# ProPrj_minibal.net
KiCad netlist of a schematic drawn in EasyEDA Pro
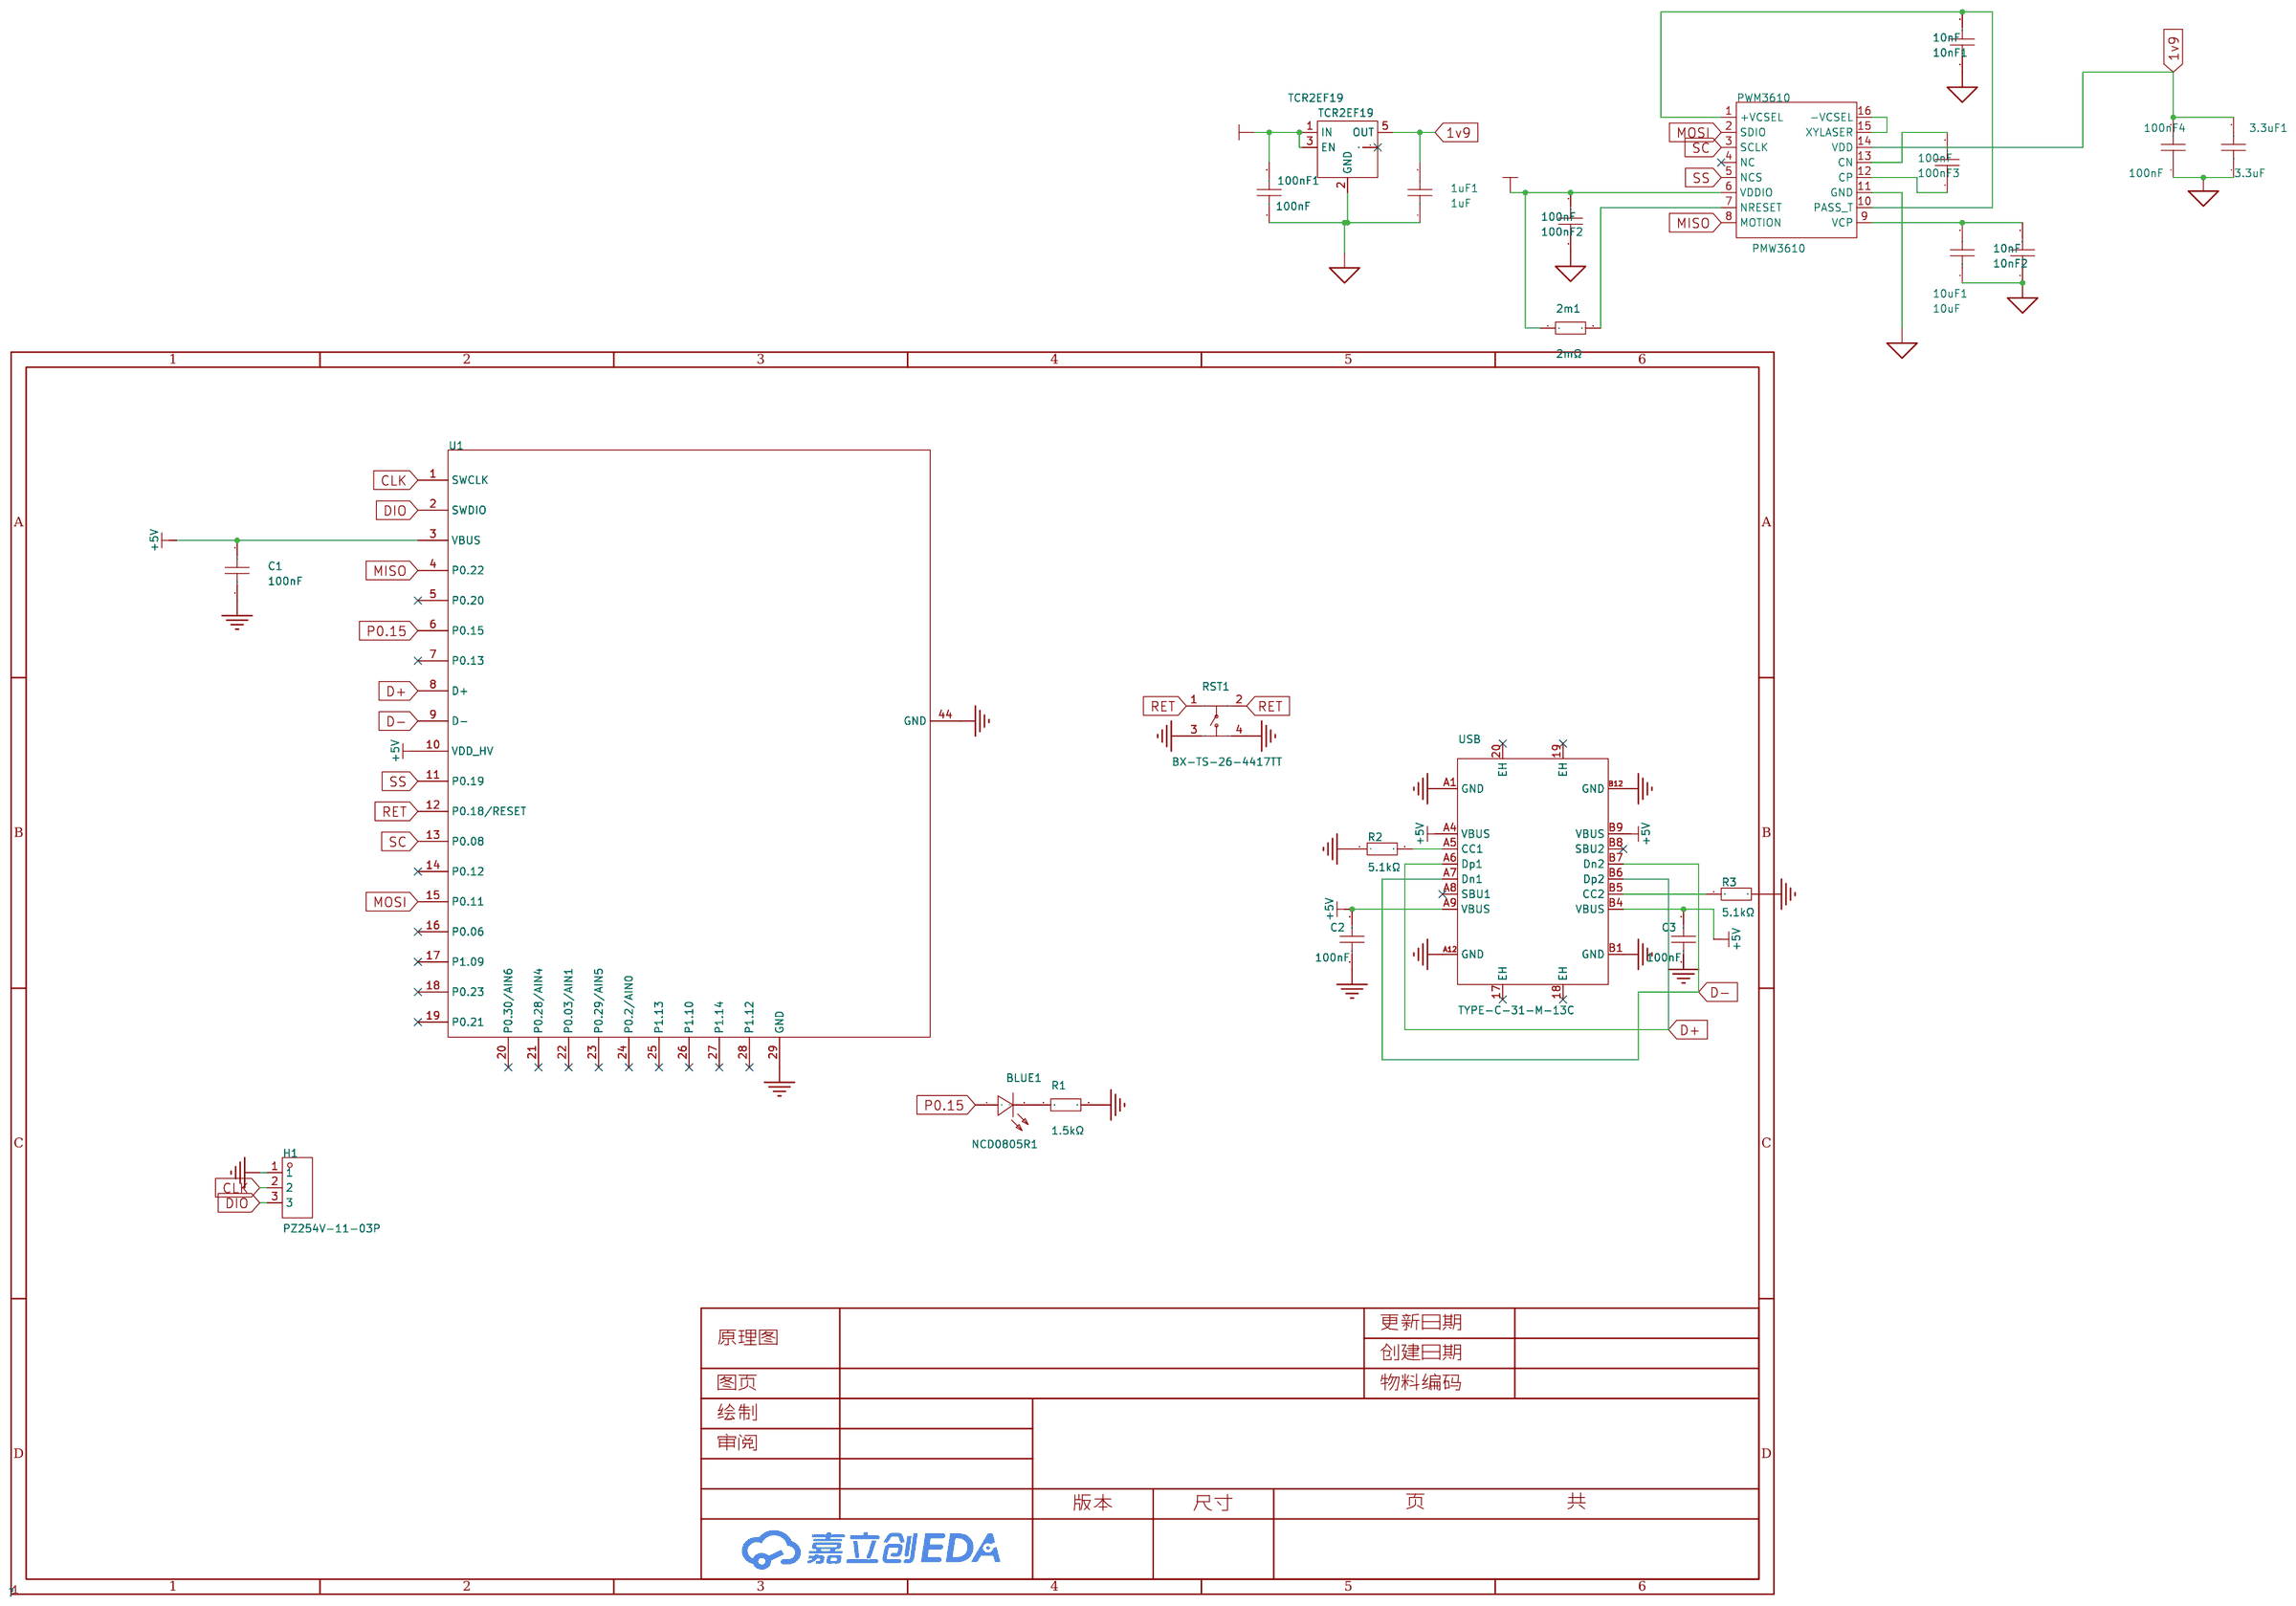
[diagram p0: schematic sheet]

(export (version "E")
  (design (tool "Eeschema 10.0.6"))
  (components
    (comp (ref "1uF1")
      (value "1uF")
      (footprint "easyedapro:C0603")
      (fields
        (field (name "Manufacturer Part") "CL21B105KBFNNNE")
        (field (name "Manufacturer") "SAMSUNG(三星)")
      )
      (libsource (lib "easyedapro") (part "CapAcitance"))
    )
    (comp (ref "2m1")
      (value "2mΩ")
      (fields (field (name "Manufacturer Part") "RLM10FTSMR002") (field (name "Manufacturer") "大毅科技"))
      (libsource (lib "easyedapro") (part "电阻"))
    )
    (comp (ref "3.3uF1")
      (value "3.3uF")
      (footprint "easyedapro:C0603")
      (fields (field (name "Manufacturer Part") "0805B335K160NT") (field (name "Manufacturer") "FH(风华)"))
      (libsource (lib "easyedapro") (part "CapAcitance"))
    )
    (comp (ref "10nF1")
      (value "10nF")
      (footprint "easyedapro:C0603")
      (fields
        (field (name "Manufacturer Part") "CC0805KRX7R9BB103")
        (field (name "Manufacturer") "YAGEO(国巨)")
      )
      (libsource (lib "easyedapro") (part "CapAcitance"))
    )
    (comp (ref "10nF2")
      (value "10nF")
      (footprint "easyedapro:C0603")
      (fields
        (field (name "Manufacturer Part") "CC0805KRX7R9BB103")
        (field (name "Manufacturer") "YAGEO(国巨)")
      )
      (libsource (lib "easyedapro") (part "CapAcitance"))
    )
    (comp (ref "10uF1")
      (value "10uF")
      (footprint "easyedapro:C0603")
      (fields
        (field (name "Manufacturer Part") "CL21A106KOQNNNE")
        (field (name "Manufacturer") "SAMSUNG(三星)")
      )
      (libsource (lib "easyedapro") (part "CapAcitance"))
    )
    (comp (ref "100nF1")
      (value "100nF")
      (footprint "easyedapro:C0603")
      (fields (field (name "Manufacturer Part") "0805B104K500NT") (field (name "Manufacturer") "FH(风华)"))
      (libsource (lib "easyedapro") (part "CapAcitance"))
    )
    (comp (ref "100nF2")
      (value "100nF")
      (footprint "easyedapro:C0603")
      (fields (field (name "Manufacturer Part") "0805B104K500NT") (field (name "Manufacturer") "FH(风华)"))
      (libsource (lib "easyedapro") (part "CapAcitance"))
    )
    (comp (ref "100nF3")
      (value "100nF")
      (footprint "easyedapro:C0603")
      (fields (field (name "Manufacturer Part") "0805B104K500NT") (field (name "Manufacturer") "FH(风华)"))
      (libsource (lib "easyedapro") (part "CapAcitance"))
    )
    (comp (ref "100nF4")
      (value "100nF")
      (footprint "easyedapro:C0603")
      (fields (field (name "Manufacturer Part") "0805B104K500NT") (field (name "Manufacturer") "FH(风华)"))
      (libsource (lib "easyedapro") (part "CapAcitance"))
    )
    (comp (ref "BLUE1")
      (value "NCD0805R1")
      (footprint "easyedapro:LED0805-R-RD")
      (fields (field (name "Manufacturer") "国星光电"))
      (libsource (lib "easyedapro") (part "FC-2012HRK-620D"))
    )
    (comp (ref "C1")
      (value "100nF")
      (footprint "easyedapro:C0603")
      (fields
        (field (name "Manufacturer Part") "CC0603KRX7R9BB104")
        (field (name "Manufacturer") "YAGEO(国巨)")
      )
      (libsource (lib "easyedapro") (part "CapAcitance"))
    )
    (comp (ref "C2")
      (value "100nF")
      (footprint "easyedapro:C0603")
      (libsource (lib "easyedapro") (part "CapAcitance"))
    )
    (comp (ref "C3")
      (value "100nF")
      (footprint "easyedapro:C0603")
      (libsource (lib "easyedapro") (part "CapAcitance"))
    )
    (comp (ref "H1")
      (value "PZ254V-11-03P")
      (footprint "easyedapro:HDR-TH_3P-P2.54-V-M")
      (fields (field (name "Manufacturer") "XFCN(兴飞)"))
      (libsource (lib "easyedapro") (part "PZ254V-11-03P_C2937625"))
    )
    (comp (ref "PWM3610")
      (value "PMW3610")
      (footprint "easyedapro:mylib:PMW3610")
      (libsource (lib "easyedapro") (part "mysymbol_PMW3610"))
    )
    (comp (ref "R1")
      (value "1.5kΩ")
      (footprint "easyedapro:R0805")
      (description "电阻类型:厚膜电阻;阻值:1.5kΩ;精度:±1%;功率:125mW;最大工作电压:150V;温度系数:±100ppm/°C;")
      (fields
        (field (name "Manufacturer Part") "0805W8F1501T5E")
        (field (name "Manufacturer") "UNI-ROYAL(厚声)")
      )
      (libsource (lib "easyedapro") (part "0805W8F1501T5E"))
    )
    (comp (ref "R2")
      (value "5.1kΩ")
      (footprint "easyedapro:R0805")
      (description "电阻类型:厚膜电阻;阻值:5.1kΩ;精度:±1%;功率:125mW;最大工作电压:150V;温度系数:±100ppm/°C;")
      (fields
        (field (name "Manufacturer Part") "0805W8F5101T5E")
        (field (name "Manufacturer") "UNI-ROYAL(厚声)")
      )
      (libsource (lib "easyedapro") (part "0805W8F5101T5E"))
    )
    (comp (ref "R3")
      (value "5.1kΩ")
      (footprint "easyedapro:R0805")
      (description "电阻类型:厚膜电阻;阻值:5.1kΩ;精度:±1%;功率:125mW;最大工作电压:150V;温度系数:±100ppm/°C;")
      (fields
        (field (name "Manufacturer Part") "0805W8F5101T5E")
        (field (name "Manufacturer") "UNI-ROYAL(厚声)")
      )
      (libsource (lib "easyedapro") (part "0805W8F5101T5E"))
    )
    (comp (ref "RST1")
      (value "BX-TS-26-4417TT")
      (footprint "easyedapro:SW-SMD_4P-L5.2-W5.2-P3.70-LS6.5")
      (fields (field (name "Manufacturer") "Bossie(博锡)"))
      (libsource (lib "easyedapro") (part "BX-TS-26-4417TT"))
    )
    (comp (ref "TCR2EF19")
      (value "TCR2EF19")
      (footprint "easyedapro:Package_TO_SOT_SMD:SOT-23-5")
      (libsource (lib "easyedapro") (part "Regulator_Linear_TLV70218_SOT23-5"))
    )
    (comp (ref "U1")
      (value "N52840")
      (footprint "easyedapro:52840MICRO-v1")
      (libsource (lib "easyedapro") (part "52840micro"))
    )
    (comp (ref "USB")
      (value "TYPE-C-31-M-13C")
      (footprint "easyedapro:USB-C-SMD_TYPE-C-31-M-13C")
      (description "连接器类型:Type-C;标准:-;公母:母;端口数量:1;触点数量:16P;安装方式:沉板;额定电流 - 电源:5A;工作温度范围:-30°C~+80°C;")
      (fields (field (name "Manufacturer") "韩国韩荣"))
      (libsource (lib "easyedapro") (part "TYPE-C-31-M-13C"))
    )
  )
  (nets
    (net (code "1") (name "+5V") (class "Default")
      (node (ref "C1") (pin "2") (pinfunction "2_2") (pintype "input"))
      (node (ref "C2") (pin "2") (pinfunction "2_2") (pintype "input"))
      (node (ref "C3") (pin "2") (pinfunction "2_2") (pintype "input"))
      (node (ref "U1") (pin "10") (pinfunction "VDD_HV_10") (pintype "input"))
      (node (ref "U1") (pin "3") (pinfunction "VBUS_3") (pintype "input"))
      (node (ref "USB") (pin "A4") (pinfunction "VBUS_A4") (pintype "unspecified"))
      (node (ref "USB") (pin "A9") (pinfunction "VBUS_A9") (pintype "unspecified"))
      (node (ref "USB") (pin "B4") (pinfunction "VBUS_B4") (pintype "unspecified"))
      (node (ref "USB") (pin "B9") (pinfunction "VBUS_B9") (pintype "unspecified"))
    )
    (net (code "2") (name "1v9") (class "Default")
      (node (ref "100nF4") (pin "2") (pinfunction "2_2") (pintype "input"))
      (node (ref "1uF1") (pin "2") (pinfunction "2_2") (pintype "input"))
      (node (ref "3.3uF1") (pin "2") (pinfunction "2_2") (pintype "input"))
      (node (ref "PWM3610") (pin "14") (pinfunction "VDD_14") (pintype "unspecified"))
      (node (ref "TCR2EF19") (pin "5") (pinfunction "OUT_5") (pintype "unspecified"))
    )
    (net (code "3") (name "CLK") (class "Default")
      (node (ref "H1") (pin "2") (pinfunction "2_2") (pintype "unspecified"))
      (node (ref "U1") (pin "1") (pinfunction "SWCLK_1") (pintype "input"))
    )
    (net (code "4") (name "D+") (class "Default")
      (node (ref "U1") (pin "8") (pinfunction "D+_8") (pintype "input"))
      (node (ref "USB") (pin "A6") (pinfunction "Dp1_A6") (pintype "unspecified"))
      (node (ref "USB") (pin "B6") (pinfunction "Dp2_B6") (pintype "unspecified"))
    )
    (net (code "5") (name "D-") (class "Default")
      (node (ref "U1") (pin "9") (pinfunction "D-_9") (pintype "input"))
      (node (ref "USB") (pin "A7") (pinfunction "Dn1_A7") (pintype "unspecified"))
      (node (ref "USB") (pin "B7") (pinfunction "Dn2_B7") (pintype "unspecified"))
    )
    (net (code "6") (name "DIO") (class "Default")
      (node (ref "H1") (pin "3") (pinfunction "3_3") (pintype "unspecified"))
      (node (ref "U1") (pin "2") (pinfunction "SWDIO_2") (pintype "input"))
    )
    (net (code "7") (name "GND") (class "Default")
      (node (ref "100nF1") (pin "1") (pinfunction "1_1") (pintype "input"))
      (node (ref "100nF2") (pin "1") (pinfunction "1_1") (pintype "input"))
      (node (ref "100nF4") (pin "1") (pinfunction "1_1") (pintype "input"))
      (node (ref "10nF1") (pin "1") (pinfunction "1_1") (pintype "input"))
      (node (ref "10nF2") (pin "1") (pinfunction "1_1") (pintype "input"))
      (node (ref "10uF1") (pin "1") (pinfunction "1_1") (pintype "input"))
      (node (ref "1uF1") (pin "1") (pinfunction "1_1") (pintype "input"))
      (node (ref "3.3uF1") (pin "1") (pinfunction "1_1") (pintype "input"))
      (node (ref "C1") (pin "1") (pinfunction "1_1") (pintype "input"))
      (node (ref "C2") (pin "1") (pinfunction "1_1") (pintype "input"))
      (node (ref "C3") (pin "1") (pinfunction "1_1") (pintype "input"))
      (node (ref "H1") (pin "1") (pinfunction "1_1") (pintype "unspecified"))
      (node (ref "PWM3610") (pin "11") (pinfunction "GND_11") (pintype "input"))
      (node (ref "R1") (pin "2") (pinfunction "2_2") (pintype "input"))
      (node (ref "R2") (pin "1") (pinfunction "1_1") (pintype "input"))
      (node (ref "R3") (pin "2") (pinfunction "2_2") (pintype "input"))
      (node (ref "RST1") (pin "3") (pinfunction "3_3") (pintype "unspecified"))
      (node (ref "RST1") (pin "4") (pinfunction "4_4") (pintype "unspecified"))
      (node (ref "TCR2EF19") (pin "2") (pinfunction "GND_2") (pintype "unspecified"))
      (node (ref "U1") (pin "29") (pinfunction "GND_29") (pintype "input"))
      (node (ref "U1") (pin "44") (pinfunction "GND_44") (pintype "input"))
      (node (ref "USB") (pin "A1") (pinfunction "GND_A1") (pintype "unspecified"))
      (node (ref "USB") (pin "A12") (pinfunction "GND_A12") (pintype "unspecified"))
      (node (ref "USB") (pin "B1") (pinfunction "GND_B1") (pintype "unspecified"))
      (node (ref "USB") (pin "B12") (pinfunction "GND_B12") (pintype "unspecified"))
    )
    (net (code "8") (name "MISO") (class "Default")
      (node (ref "PWM3610") (pin "8") (pinfunction "MOTION_8") (pintype "output"))
      (node (ref "U1") (pin "4") (pinfunction "P0.22_4") (pintype "input"))
    )
    (net (code "9") (name "MOSI") (class "Default")
      (node (ref "PWM3610") (pin "2") (pinfunction "SDIO_2") (pintype "bidirectional"))
      (node (ref "U1") (pin "15") (pinfunction "P0.11_15") (pintype "input"))
    )
    (net (code "10") (name "Net-(BLUE1--)") (class "Default")
      (node (ref "BLUE1") (pin "2") (pinfunction "-_2") (pintype "unspecified"))
      (node (ref "R1") (pin "1") (pinfunction "1_1") (pintype "input"))
    )
    (net (code "11") (name "Net-(PWM3610-+VCSEL)") (class "Default")
      (node (ref "10nF1") (pin "2") (pinfunction "2_2") (pintype "input"))
      (node (ref "PWM3610") (pin "1") (pinfunction "+VCSEL_1") (pintype "input"))
      (node (ref "PWM3610") (pin "10") (pinfunction "PASS_T_10") (pintype "unspecified"))
    )
    (net (code "12") (name "Net-(PWM3610--VCSEL)") (class "Default")
      (node (ref "PWM3610") (pin "15") (pinfunction "XYLASER_15") (pintype "input"))
      (node (ref "PWM3610") (pin "16") (pinfunction "-VCSEL_16") (pintype "unspecified"))
    )
    (net (code "13") (name "Net-(PWM3610-CN)") (class "Default")
      (node (ref "100nF3") (pin "2") (pinfunction "2_2") (pintype "input"))
      (node (ref "PWM3610") (pin "13") (pinfunction "CN_13") (pintype "unspecified"))
    )
    (net (code "14") (name "Net-(PWM3610-CP)") (class "Default")
      (node (ref "100nF3") (pin "1") (pinfunction "1_1") (pintype "input"))
      (node (ref "PWM3610") (pin "12") (pinfunction "CP_12") (pintype "unspecified"))
    )
    (net (code "15") (name "Net-(PWM3610-NRESET)") (class "Default")
      (node (ref "2m1") (pin "2") (pinfunction "2_2") (pintype "input"))
      (node (ref "PWM3610") (pin "7") (pinfunction "NRESET_7") (pintype "input"))
    )
    (net (code "16") (name "Net-(PWM3610-VCP)") (class "Default")
      (node (ref "10nF2") (pin "2") (pinfunction "2_2") (pintype "input"))
      (node (ref "10uF1") (pin "2") (pinfunction "2_2") (pintype "input"))
      (node (ref "PWM3610") (pin "9") (pinfunction "VCP_9") (pintype "unspecified"))
    )
    (net (code "17") (name "Net-(USB-CC1)") (class "Default")
      (node (ref "R2") (pin "2") (pinfunction "2_2") (pintype "input"))
      (node (ref "USB") (pin "A5") (pinfunction "CC1_A5") (pintype "unspecified"))
    )
    (net (code "18") (name "Net-(USB-CC2)") (class "Default")
      (node (ref "R3") (pin "1") (pinfunction "1_1") (pintype "input"))
      (node (ref "USB") (pin "B5") (pinfunction "CC2_B5") (pintype "unspecified"))
    )
    (net (code "19") (name "P0.15") (class "Default")
      (node (ref "BLUE1") (pin "1") (pinfunction "+_1") (pintype "unspecified"))
      (node (ref "U1") (pin "6") (pinfunction "P0.15_6") (pintype "input"))
    )
    (net (code "20") (name "RET") (class "Default")
      (node (ref "RST1") (pin "1") (pinfunction "1_1") (pintype "unspecified"))
      (node (ref "RST1") (pin "2") (pinfunction "2_2") (pintype "unspecified"))
      (node (ref "U1") (pin "12") (pinfunction "P0.18/RESET_12") (pintype "input"))
    )
    (net (code "21") (name "SC") (class "Default")
      (node (ref "PWM3610") (pin "3") (pinfunction "SCLK_3") (pintype "input"))
      (node (ref "U1") (pin "13") (pinfunction "P0.08_13") (pintype "input"))
    )
    (net (code "22") (name "SS") (class "Default")
      (node (ref "PWM3610") (pin "5") (pinfunction "NCS_5") (pintype "input"))
      (node (ref "U1") (pin "11") (pinfunction "P0.19_11") (pintype "input"))
    )
    (net (code "23") (name "VCC_EXT") (class "Default")
      (node (ref "100nF1") (pin "2") (pinfunction "2_2") (pintype "input"))
      (node (ref "100nF2") (pin "2") (pinfunction "2_2") (pintype "input"))
      (node (ref "2m1") (pin "1") (pinfunction "1_1") (pintype "input"))
      (node (ref "PWM3610") (pin "6") (pinfunction "VDDIO_6") (pintype "input"))
      (node (ref "TCR2EF19") (pin "1") (pinfunction "IN_1") (pintype "unspecified"))
      (node (ref "TCR2EF19") (pin "3") (pinfunction "EN_3") (pintype "input"))
    )
    (net (code "24") (name "unconnected-(PWM3610-NC-Pad4)") (class "Default")
      (node (ref "PWM3610") (pin "4") (pinfunction "NC_4") (pintype "unspecified+no_connect"))
    )
    (net (code "25") (name "unconnected-(TCR2EF19-NC-Pad4)") (class "Default")
      (node (ref "TCR2EF19") (pin "4") (pinfunction "NC_4") (pintype "unspecified+no_connect"))
    )
    (net (code "26") (name "unconnected-(U1-P0.2{slash}AIN0-Pad24)") (class "Default")
      (node (ref "U1") (pin "24") (pinfunction "P0.2/AIN0_24") (pintype "input+no_connect"))
    )
    (net (code "27") (name "unconnected-(U1-P0.03{slash}AIN1-Pad22)") (class "Default")
      (node (ref "U1") (pin "22") (pinfunction "P0.03/AIN1_22") (pintype "input+no_connect"))
    )
    (net (code "28") (name "unconnected-(U1-P0.06-Pad16)") (class "Default")
      (node (ref "U1") (pin "16") (pinfunction "P0.06_16") (pintype "input+no_connect"))
    )
    (net (code "29") (name "unconnected-(U1-P0.12-Pad14)") (class "Default")
      (node (ref "U1") (pin "14") (pinfunction "P0.12_14") (pintype "input+no_connect"))
    )
    (net (code "30") (name "unconnected-(U1-P0.13-Pad7)") (class "Default")
      (node (ref "U1") (pin "7") (pinfunction "P0.13_7") (pintype "input+no_connect"))
    )
    (net (code "31") (name "unconnected-(U1-P0.20-Pad5)") (class "Default")
      (node (ref "U1") (pin "5") (pinfunction "P0.20_5") (pintype "input+no_connect"))
    )
    (net (code "32") (name "unconnected-(U1-P0.21-Pad19)") (class "Default")
      (node (ref "U1") (pin "19") (pinfunction "P0.21_19") (pintype "input+no_connect"))
    )
    (net (code "33") (name "unconnected-(U1-P0.23-Pad18)") (class "Default")
      (node (ref "U1") (pin "18") (pinfunction "P0.23_18") (pintype "input+no_connect"))
    )
    (net (code "34") (name "unconnected-(U1-P0.28{slash}AIN4-Pad21)") (class "Default")
      (node (ref "U1") (pin "21") (pinfunction "P0.28/AIN4_21") (pintype "input+no_connect"))
    )
    (net (code "35") (name "unconnected-(U1-P0.29{slash}AIN5-Pad23)") (class "Default")
      (node (ref "U1") (pin "23") (pinfunction "P0.29/AIN5_23") (pintype "input+no_connect"))
    )
    (net (code "36") (name "unconnected-(U1-P0.30{slash}AIN6-Pad20)") (class "Default")
      (node (ref "U1") (pin "20") (pinfunction "P0.30/AIN6_20") (pintype "input+no_connect"))
    )
    (net (code "37") (name "unconnected-(U1-P1.09-Pad17)") (class "Default")
      (node (ref "U1") (pin "17") (pinfunction "P1.09_17") (pintype "input+no_connect"))
    )
    (net (code "38") (name "unconnected-(U1-P1.10-Pad26)") (class "Default")
      (node (ref "U1") (pin "26") (pinfunction "P1.10_26") (pintype "input+no_connect"))
    )
    (net (code "39") (name "unconnected-(U1-P1.12-Pad28)") (class "Default")
      (node (ref "U1") (pin "28") (pinfunction "P1.12_28") (pintype "input+no_connect"))
    )
    (net (code "40") (name "unconnected-(U1-P1.13-Pad25)") (class "Default")
      (node (ref "U1") (pin "25") (pinfunction "P1.13_25") (pintype "input+no_connect"))
    )
    (net (code "41") (name "unconnected-(U1-P1.14-Pad27)") (class "Default")
      (node (ref "U1") (pin "27") (pinfunction "P1.14_27") (pintype "input+no_connect"))
    )
    (net (code "42") (name "unconnected-(USB-EH-Pad17)") (class "Default")
      (node (ref "USB") (pin "17") (pinfunction "EH_17") (pintype "unspecified+no_connect"))
    )
    (net (code "43") (name "unconnected-(USB-EH-Pad18)") (class "Default")
      (node (ref "USB") (pin "18") (pinfunction "EH_18") (pintype "unspecified+no_connect"))
    )
    (net (code "44") (name "unconnected-(USB-EH-Pad19)") (class "Default")
      (node (ref "USB") (pin "19") (pinfunction "EH_19") (pintype "unspecified+no_connect"))
    )
    (net (code "45") (name "unconnected-(USB-EH-Pad20)") (class "Default")
      (node (ref "USB") (pin "20") (pinfunction "EH_20") (pintype "unspecified+no_connect"))
    )
    (net (code "46") (name "unconnected-(USB-SBU1-PadA8)") (class "Default")
      (node (ref "USB") (pin "A8") (pinfunction "SBU1_A8") (pintype "unspecified+no_connect"))
    )
    (net (code "47") (name "unconnected-(USB-SBU2-PadB8)") (class "Default")
      (node (ref "USB") (pin "B8") (pinfunction "SBU2_B8") (pintype "unspecified+no_connect"))
    )
  )
)
